# MicronetToNMEA.net
KiCad netlist of a schematic drawn in EasyEDA Pro
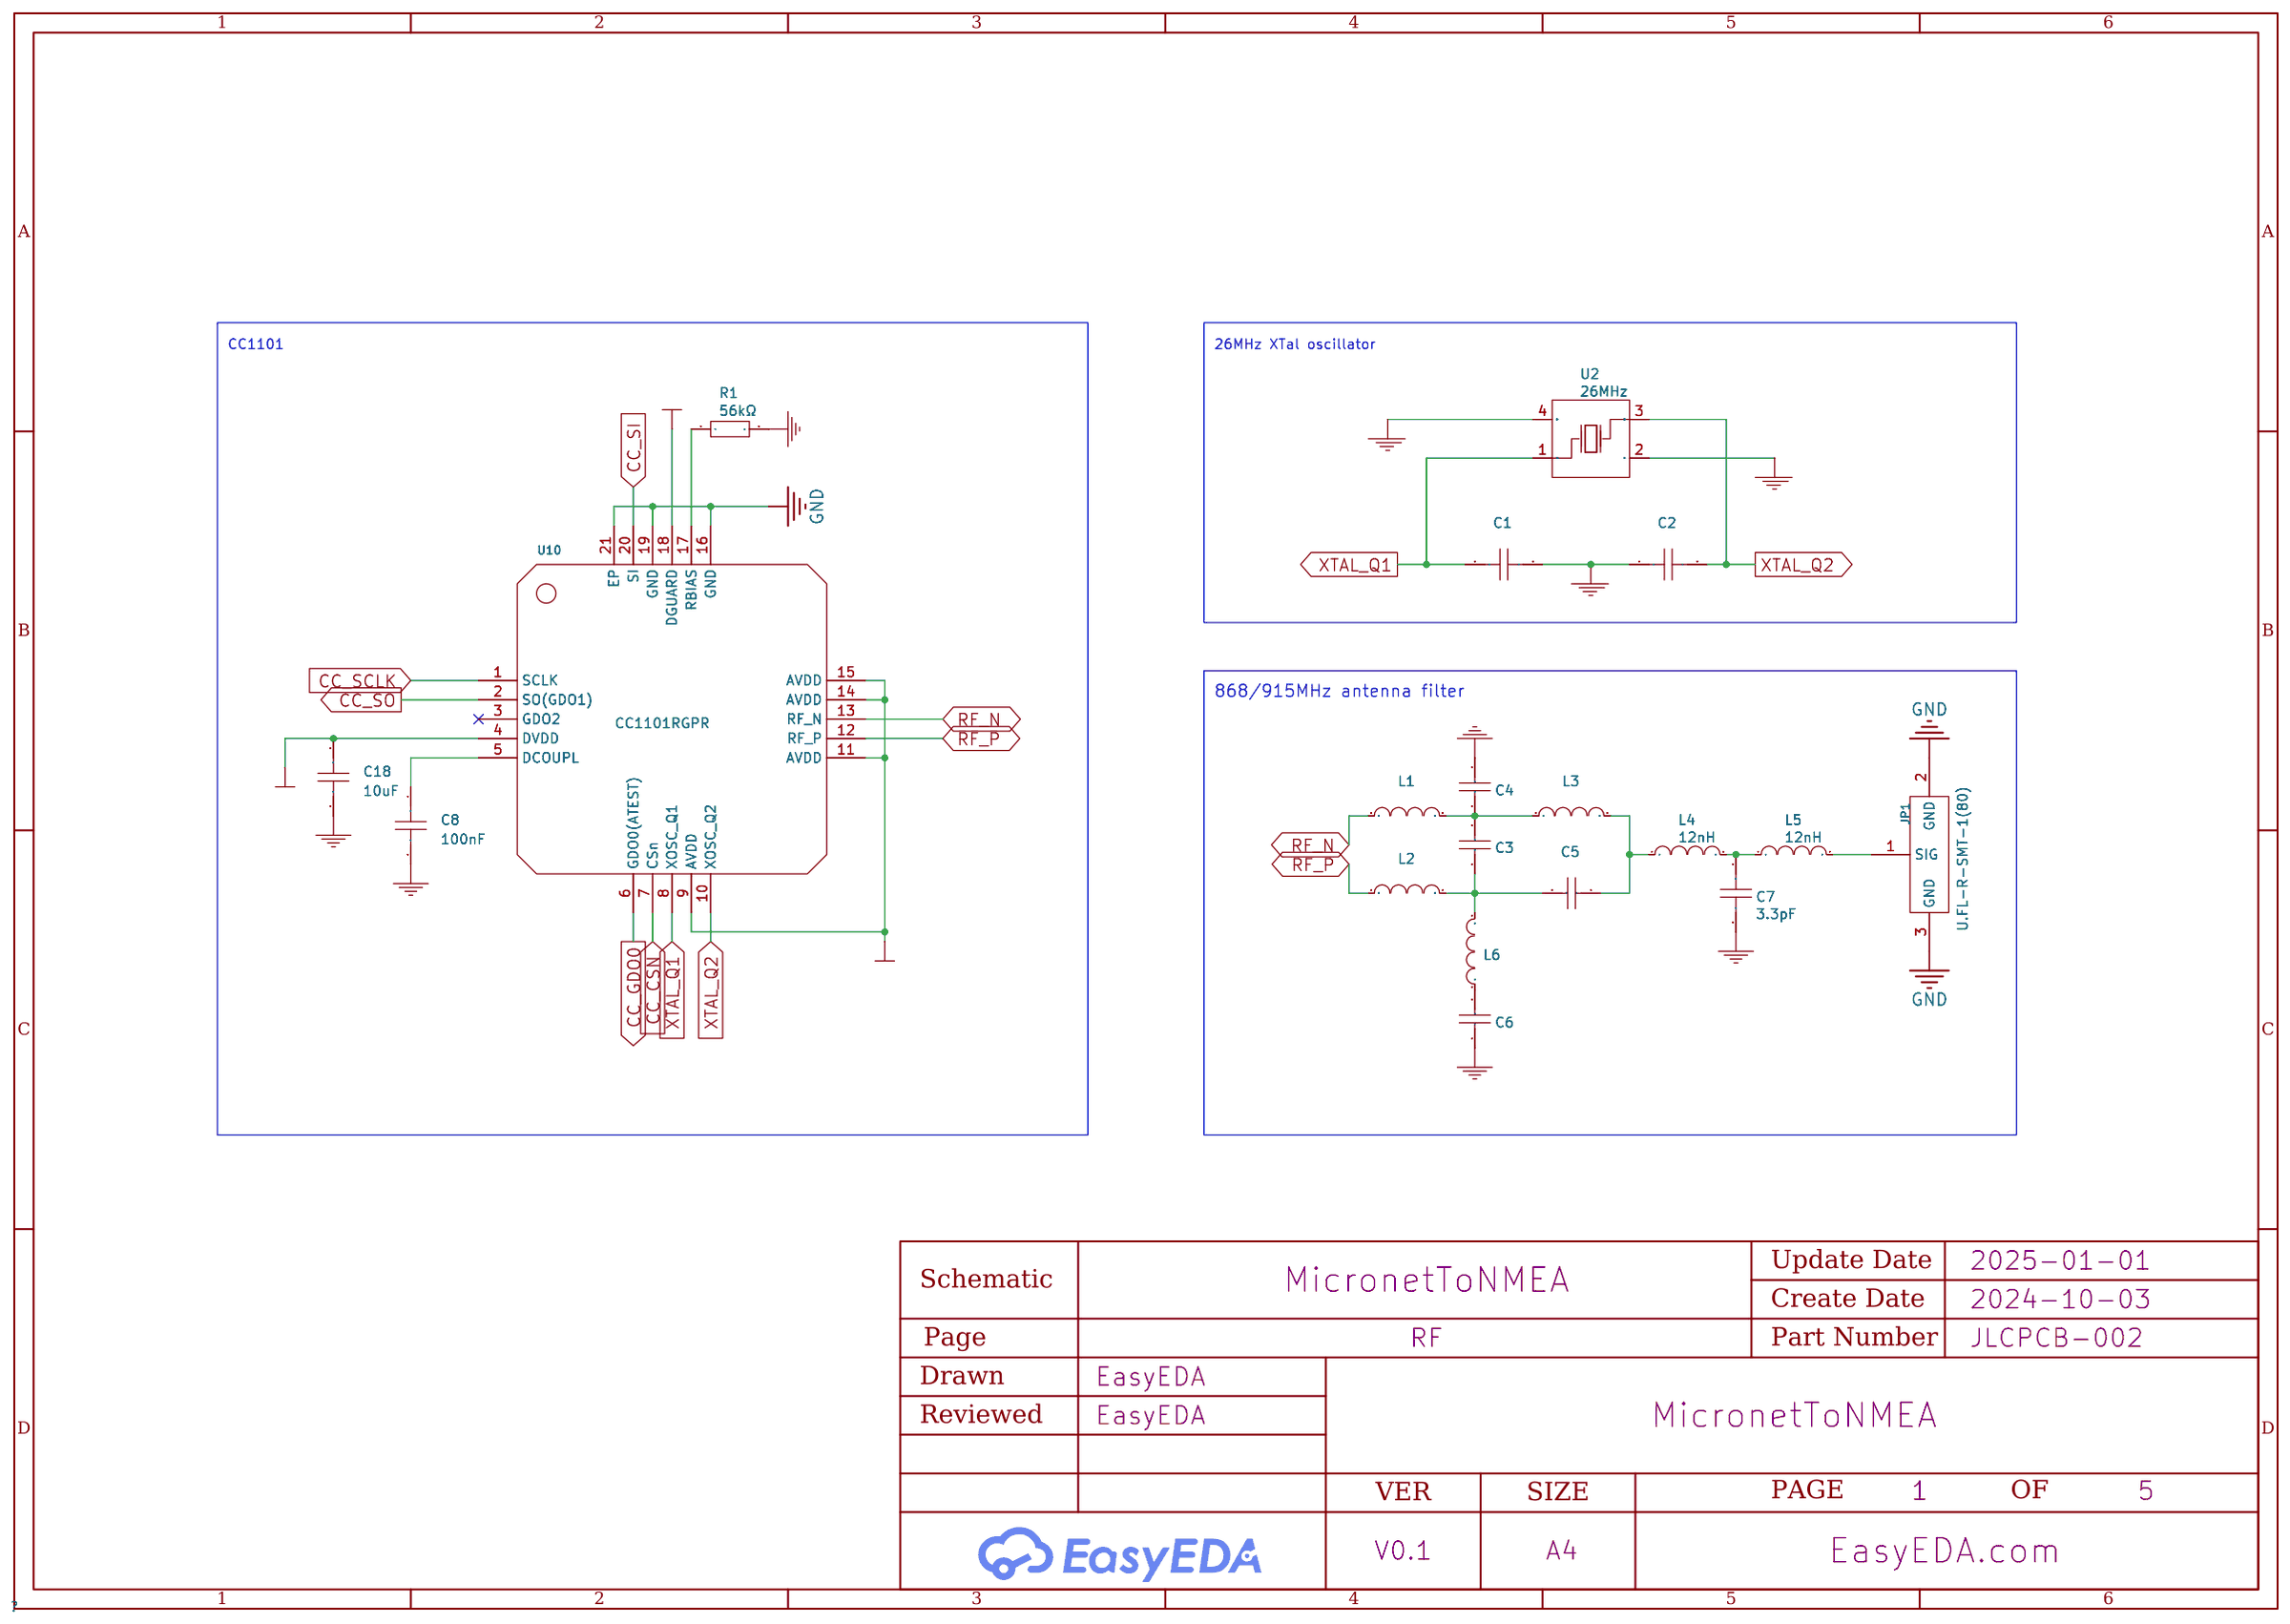
[diagram p0: RF]
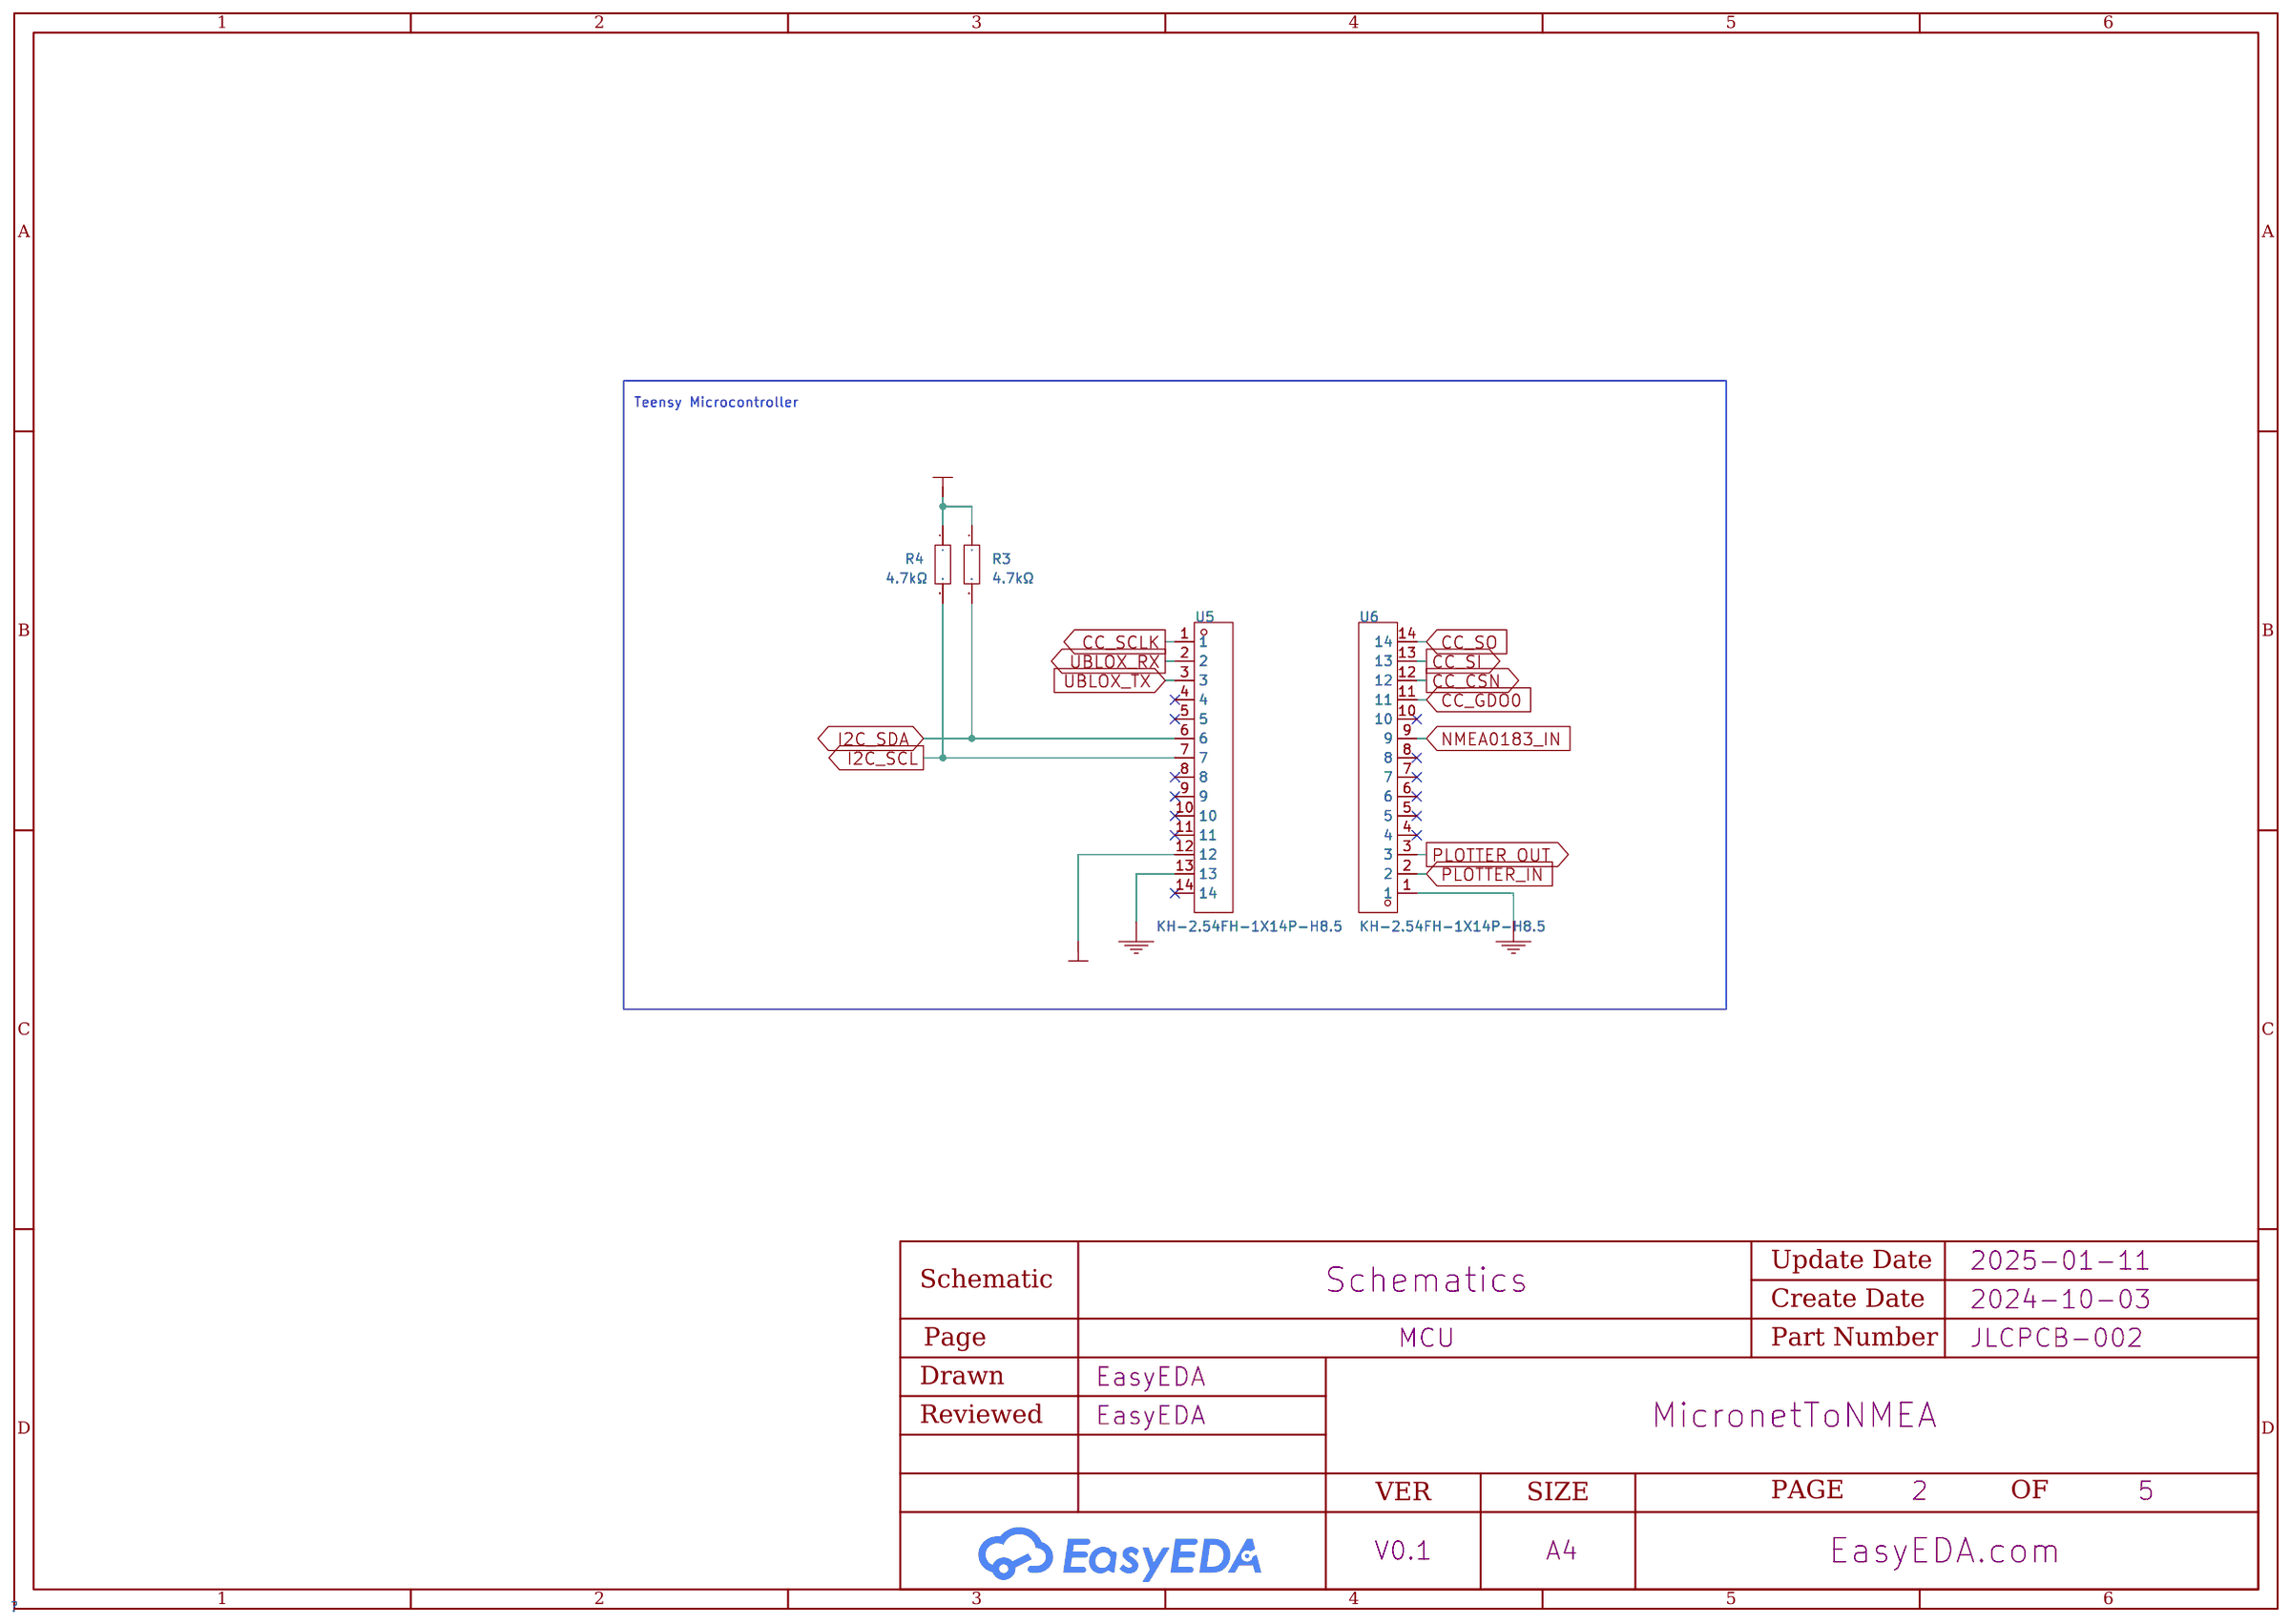
[diagram p1: MCU]
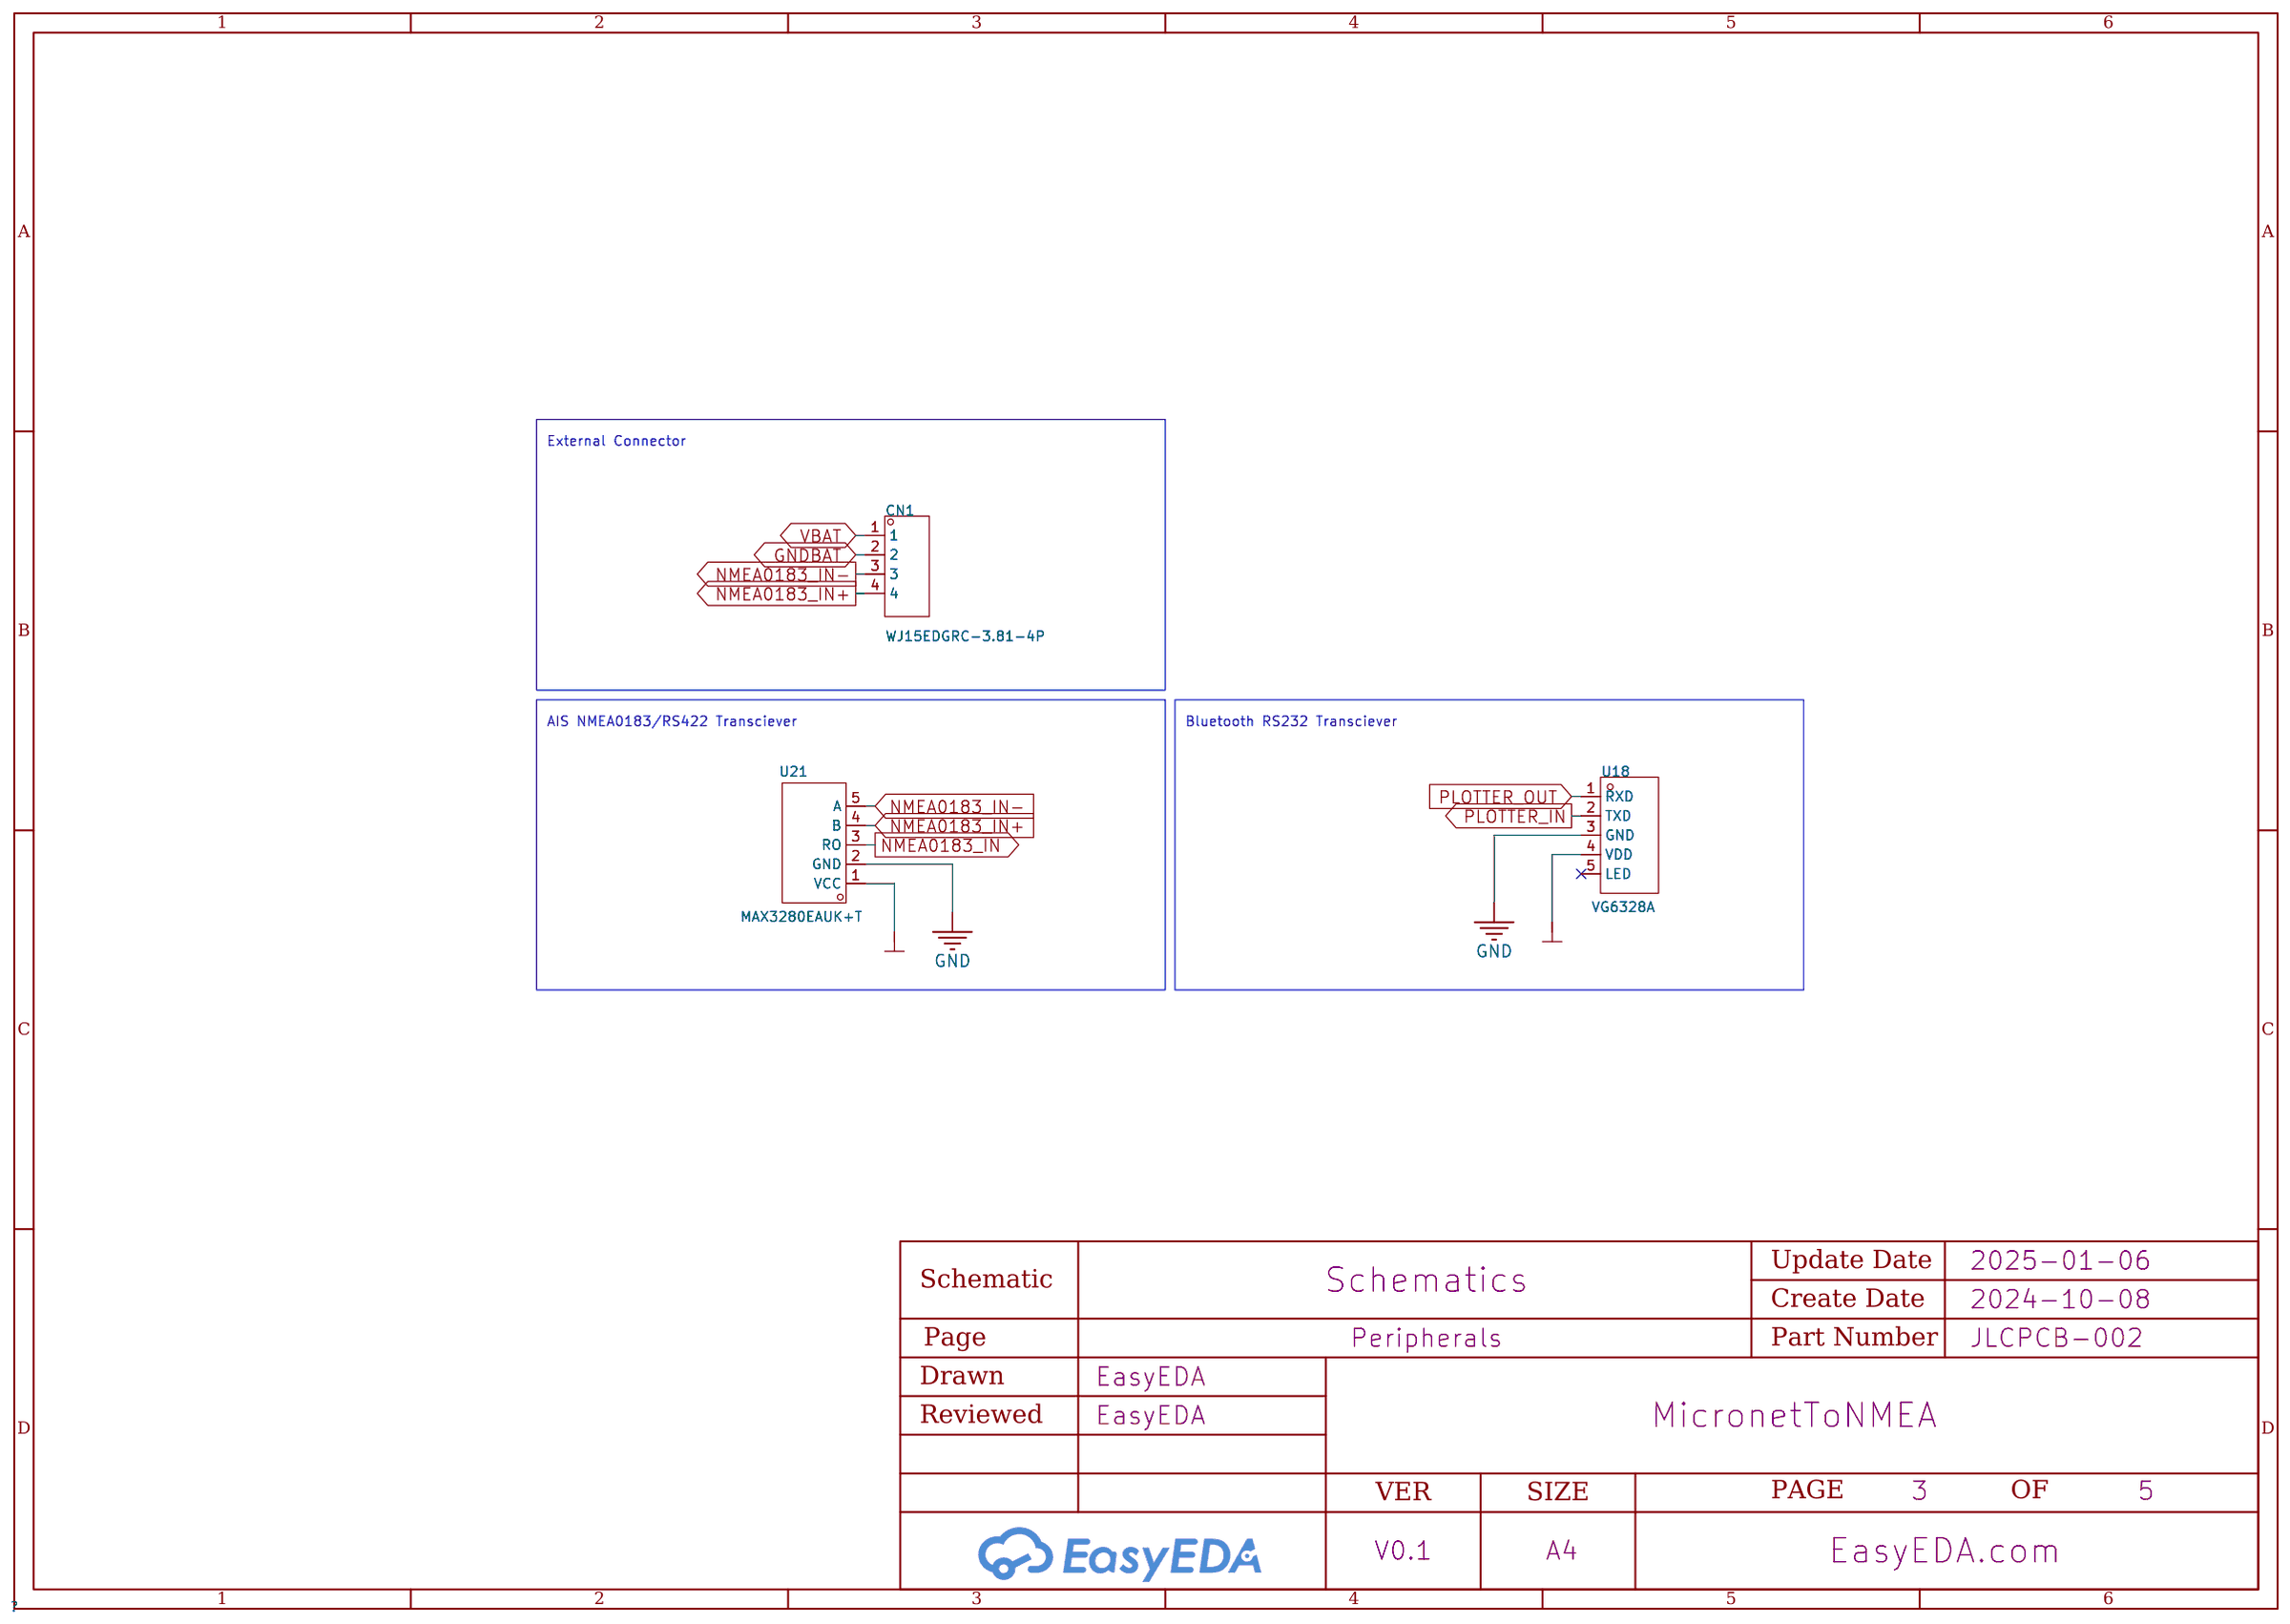
[diagram p2: Peripherals]
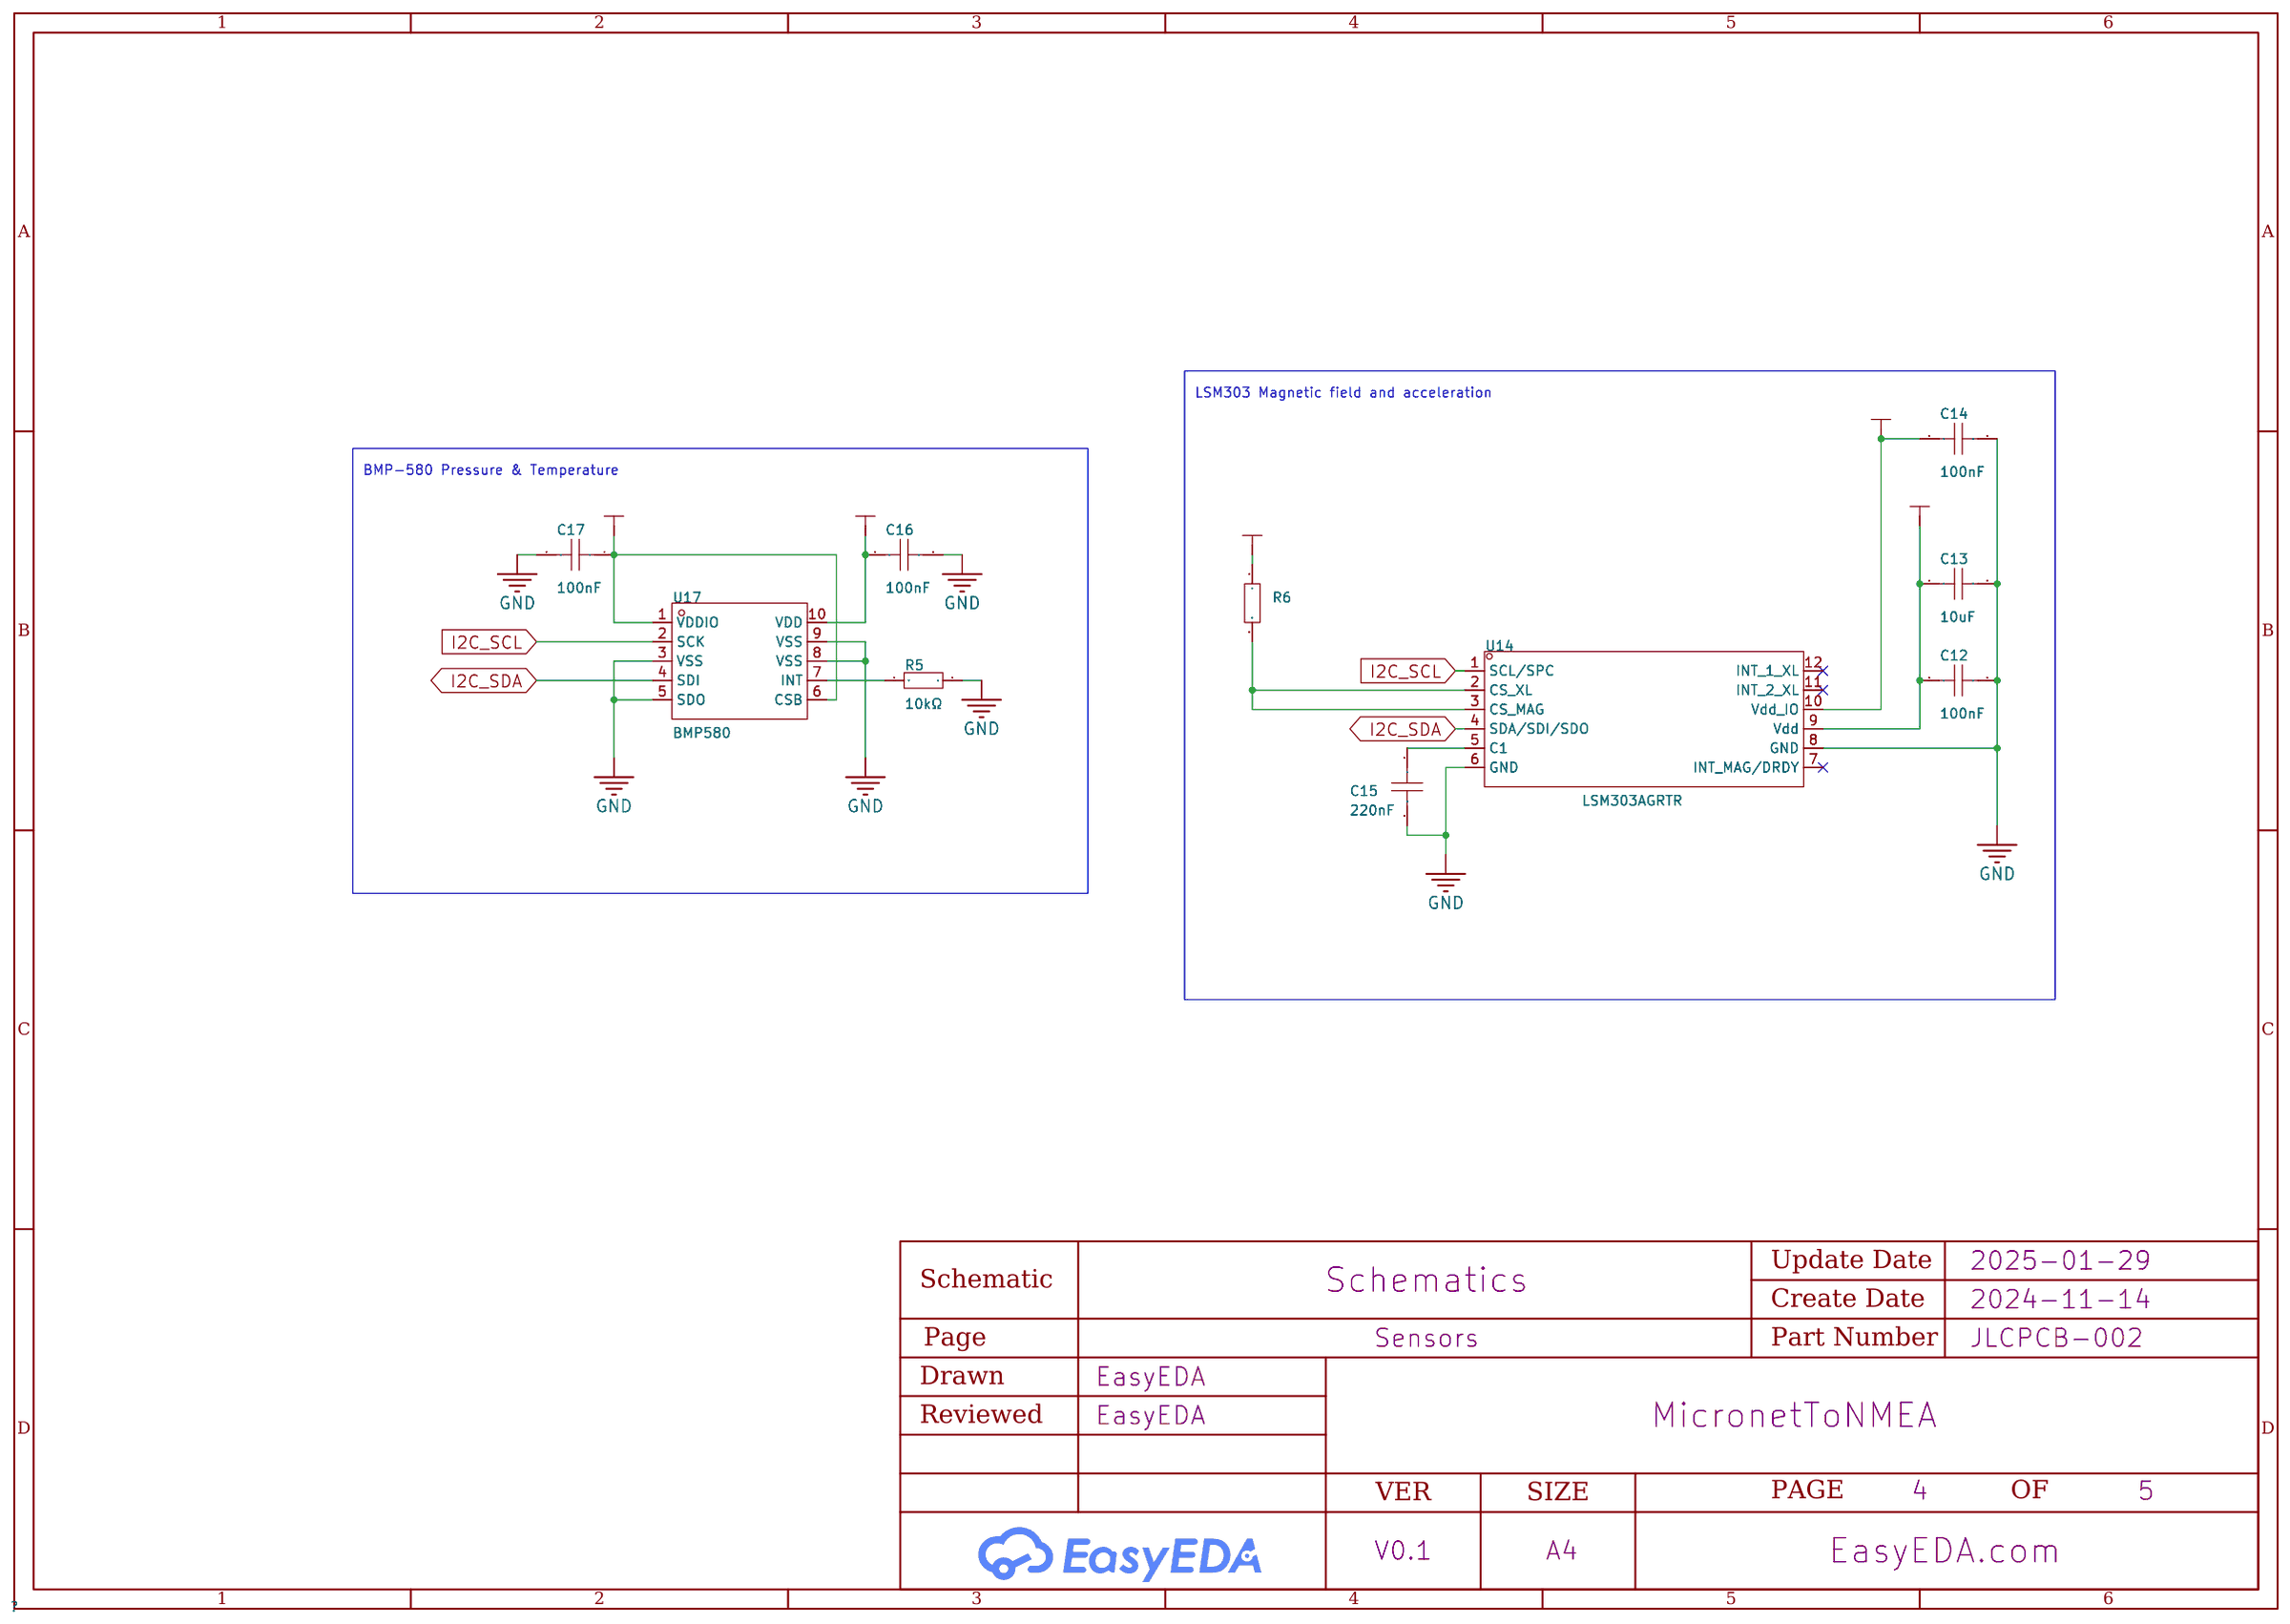
[diagram p3: Sensors]
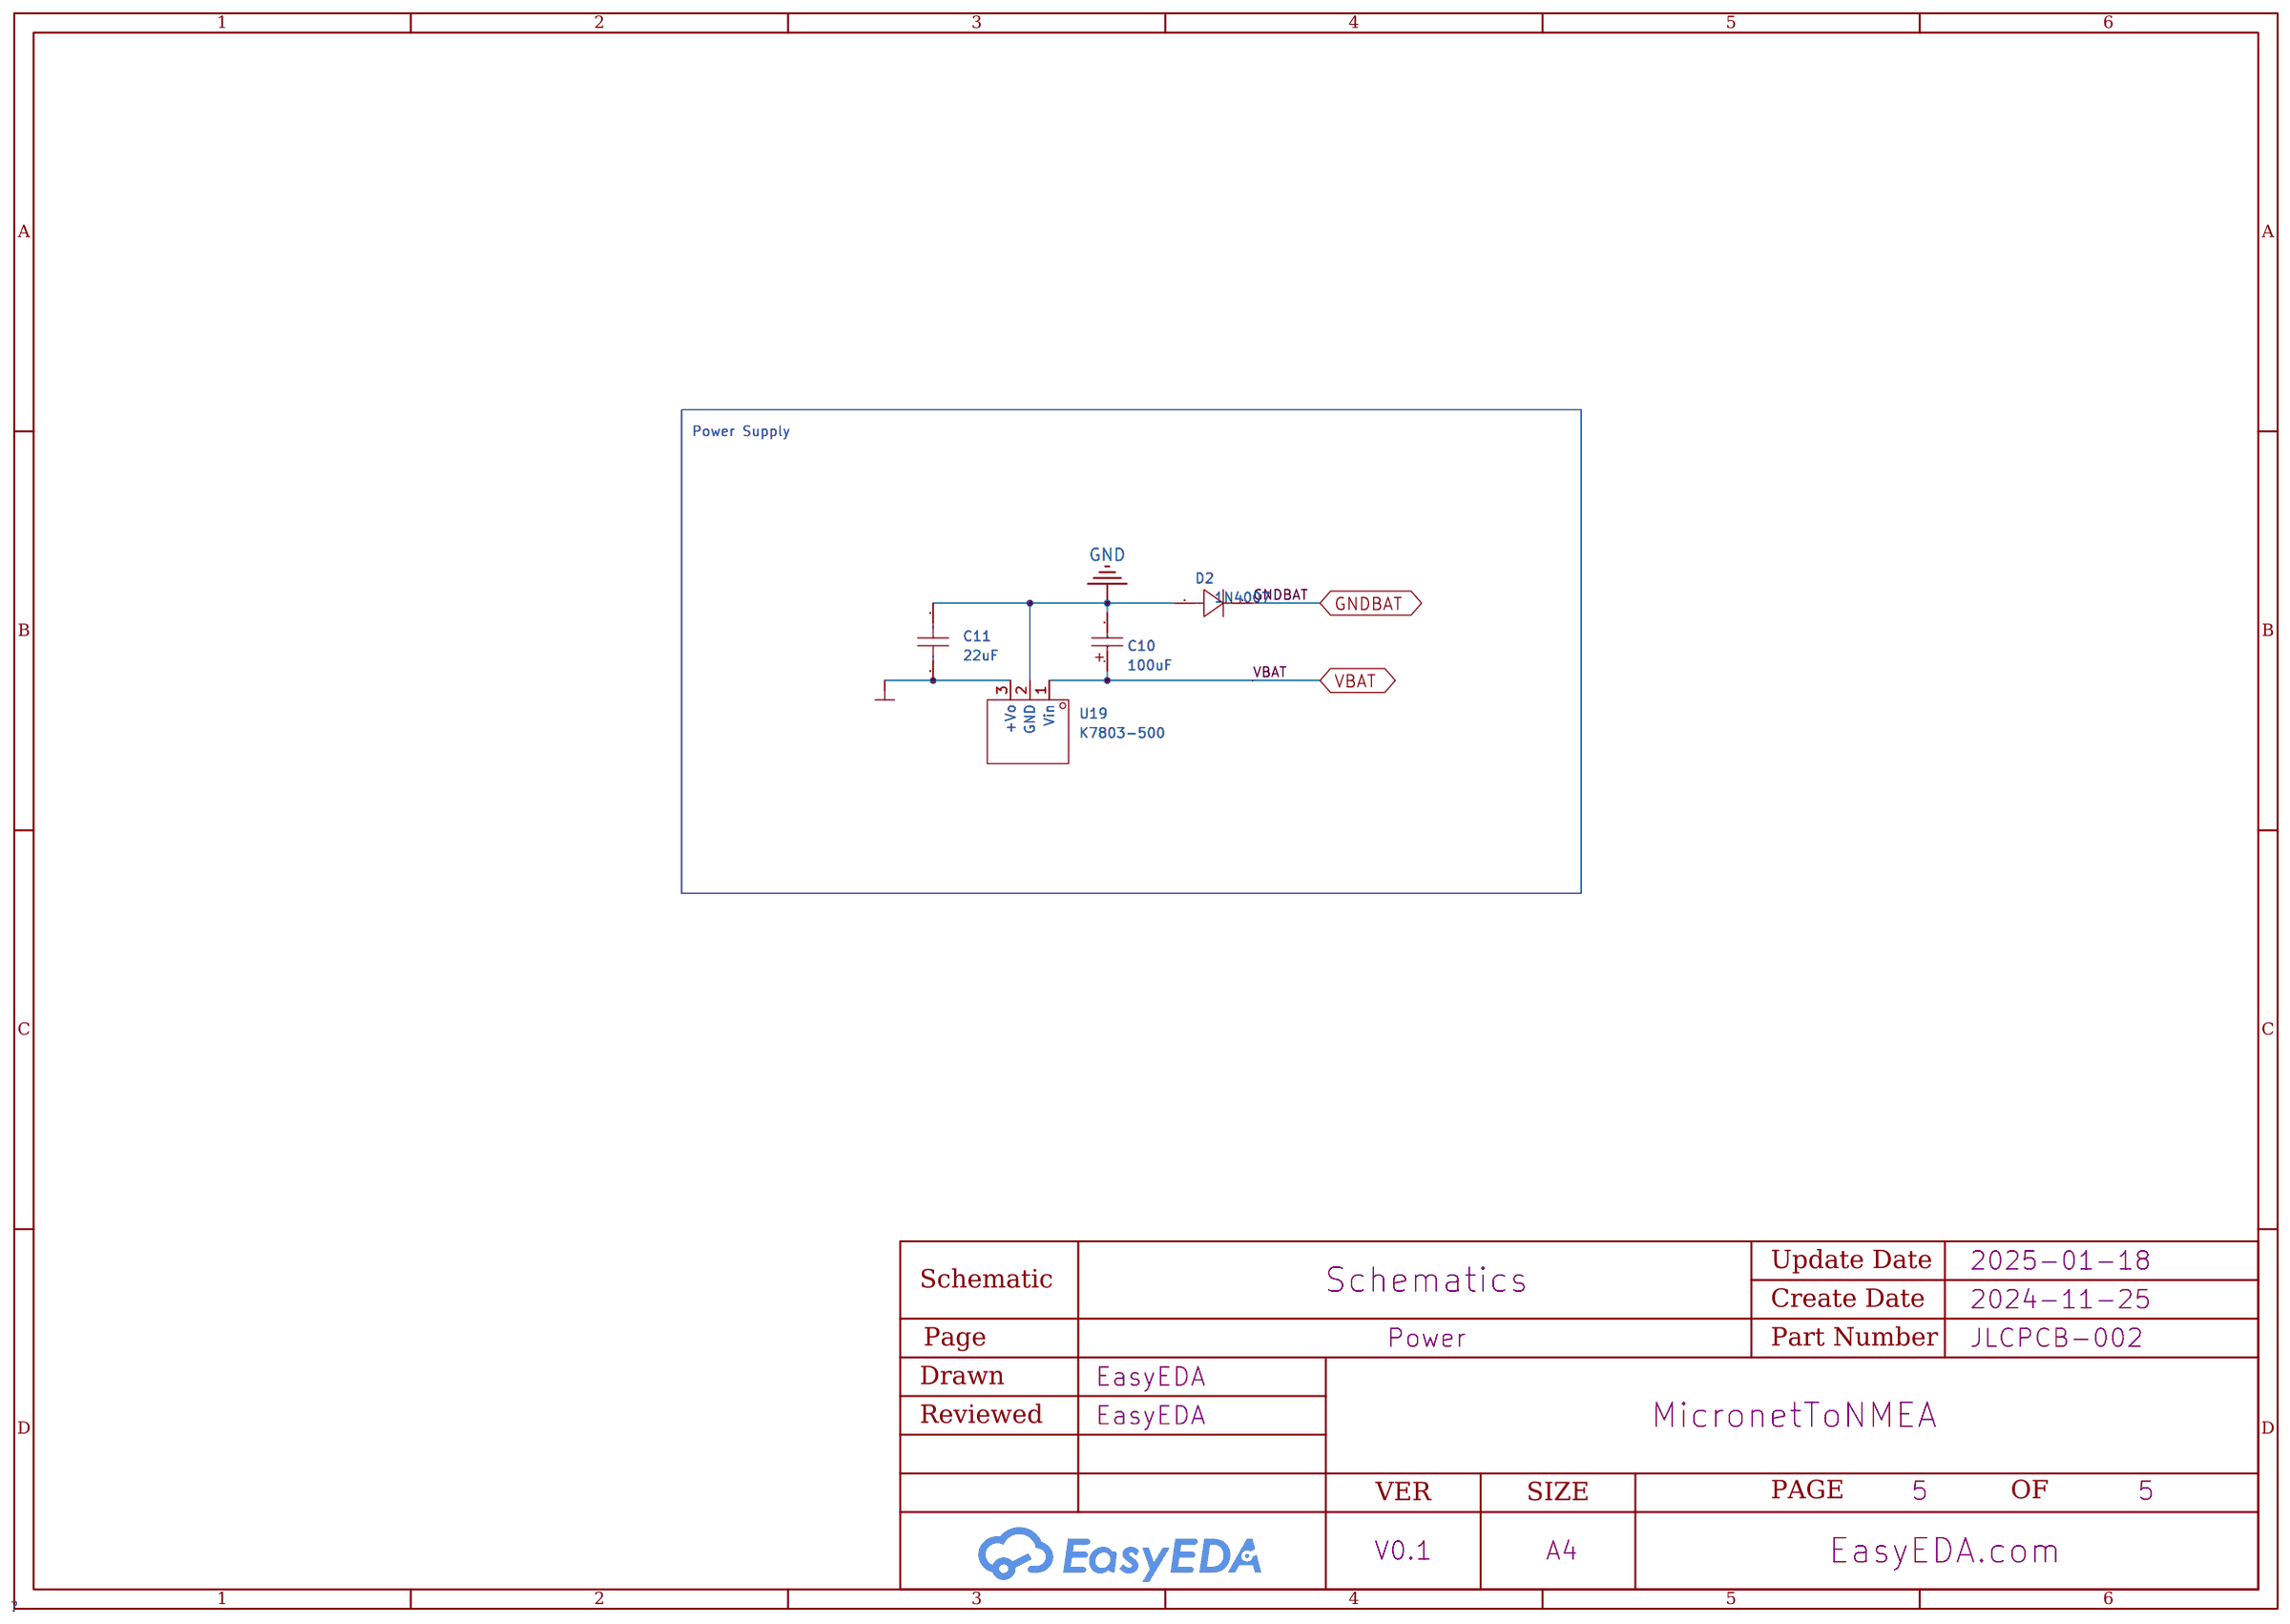
[diagram p4: Power]

(export (version "E")
  (design (tool "Eeschema 10.0.6"))
  (components
    (comp (ref "C1")
      (value "27pF")
      (footprint "easyedapro:C0402")
      (fields
        (field (name "Manufacturer Part") "GJM1555C1H270FB01D")
        (field (name "Manufacturer") "muRata(村田)")
      )
      (libsource (lib "easyedapro") (part "GJM1555C1H270FB01D"))
    )
    (comp (ref "C2")
      (value "27pF")
      (footprint "easyedapro:C0402")
      (fields
        (field (name "Manufacturer Part") "GJM1555C1H270FB01D")
        (field (name "Manufacturer") "muRata(村田)")
      )
      (libsource (lib "easyedapro") (part "GJM1555C1H270FB01D"))
    )
    (comp (ref "C3")
      (value "1pF")
      (footprint "easyedapro:C0402")
      (fields
        (field (name "Manufacturer Part") "GRM1555C1H1R0CA01D")
        (field (name "Manufacturer") "muRata(村田)")
      )
      (libsource (lib "easyedapro") (part "GRM1555C1H1R0CA01D"))
    )
    (comp (ref "C4")
      (value "1.5pF")
      (footprint "easyedapro:C0402")
      (fields
        (field (name "Manufacturer Part") "GRM1555C1H1R5BA01D")
        (field (name "Manufacturer") "muRata(村田)")
      )
      (libsource (lib "easyedapro") (part "GRM1555C1H1R5BA01D"))
    )
    (comp (ref "C5")
      (value "1.5pF")
      (footprint "easyedapro:C0402")
      (fields
        (field (name "Manufacturer Part") "GRM1555C1H1R5BA01D")
        (field (name "Manufacturer") "muRata(村田)")
      )
      (libsource (lib "easyedapro") (part "GRM1555C1H1R5BA01D"))
    )
    (comp (ref "C6")
      (value "100pF")
      (footprint "easyedapro:C0402")
      (fields
        (field (name "Manufacturer Part") "GRM1555C1H101JA01D")
        (field (name "Manufacturer") "muRata(村田)")
      )
      (libsource (lib "easyedapro") (part "GRM1555C1H101JA01D"))
    )
    (comp (ref "C7")
      (value "3.3pF")
      (fields (field (name "Manufacturer") "muRata(村田)"))
      (libsource (lib "easyedapro") (part "3.3pF"))
    )
    (comp (ref "C8")
      (value "100nF")
      (footprint "easyedapro:C0402")
      (fields
        (field (name "Manufacturer Part") "GRM155R62A104KE14D")
        (field (name "Manufacturer") "muRata(村田)")
      )
      (libsource (lib "easyedapro") (part "GRM155R62A104KE14D"))
    )
    (comp (ref "C18")
      (value "10uF")
      (footprint "easyedapro:C0402")
      (fields
        (field (name "Manufacturer Part") "GRM155R61A106ME44D")
        (field (name "Manufacturer") "muRata(村田)")
      )
      (libsource (lib "easyedapro") (part "CAP"))
    )
    (comp (ref "JP1")
      (value "U.FL-R-SMT-1(80)")
      (footprint "easyedapro:RF-SMD_FRF05002-JSS103M")
      (fields (field (name "Manufacturer") "HRS(广濑)"))
      (libsource (lib "easyedapro") (part "U.FL-R-SMT-1(80)"))
    )
    (comp (ref "L1")
      (value "12nH")
      (footprint "easyedapro:L0402")
      (fields (field (name "Manufacturer Part") "LQW15AN12NJ00D") (field (name "Manufacturer") "muRata(村田)"))
      (libsource (lib "easyedapro") (part "LQW15AN12NJ00D"))
    )
    (comp (ref "L2")
      (value "12nH")
      (footprint "easyedapro:L0402")
      (fields (field (name "Manufacturer Part") "LQW15AN12NJ00D") (field (name "Manufacturer") "muRata(村田)"))
      (libsource (lib "easyedapro") (part "LQW15AN12NJ00D"))
    )
    (comp (ref "L3")
      (value "18nH")
      (footprint "easyedapro:IND-SMD_L1.0-W0.5-2")
      (fields (field (name "Manufacturer Part") "LQW15AN18NG00D") (field (name "Manufacturer") "muRata(村田)"))
      (libsource (lib "easyedapro") (part "LQW15AN18NG00D"))
    )
    (comp (ref "L4")
      (value "12nH")
      (footprint "easyedapro:L0402")
      (fields (field (name "Manufacturer Part") "LQW15AN12NG00D") (field (name "Manufacturer") "muRata(村田)"))
      (libsource (lib "easyedapro") (part "LQW15AN12NG00D"))
    )
    (comp (ref "L5")
      (value "12nH")
      (footprint "easyedapro:L0402")
      (fields (field (name "Manufacturer Part") "LQW15AN12NG00D") (field (name "Manufacturer") "muRata(村田)"))
      (libsource (lib "easyedapro") (part "LQW15AN12NG00D"))
    )
    (comp (ref "L6")
      (value "18nH")
      (footprint "easyedapro:IND-SMD_L1.0-W0.5-2")
      (fields (field (name "Manufacturer Part") "LQW15AN18NG00D") (field (name "Manufacturer") "muRata(村田)"))
      (libsource (lib "easyedapro") (part "LQW15AN18NG00D"))
    )
    (comp (ref "R1")
      (value "56kΩ")
      (footprint "easyedapro:R0402")
      (fields (field (name "Manufacturer Part") "RK73H1ETTP5602F") (field (name "Manufacturer") "KOA"))
      (libsource (lib "easyedapro") (part "RK73H1ETTP5602F"))
    )
    (comp (ref "U2")
      (value "26MHz")
      (fields (field (name "Manufacturer Part") "NX3225GA-26MHZ-TI") (field (name "Manufacturer") "NDK"))
      (libsource (lib "easyedapro") (part "26MHz"))
    )
    (comp (ref "U10")
      (value "CC1101RGPR")
      (footprint "easyedapro:QFN-20_L4.0-W4.0-P0.5-TL-EP")
      (fields (field (name "Manufacturer") "TI(德州仪器)"))
      (libsource (lib "easyedapro") (part "CC1101RGPR"))
    )
    (comp (ref "R3")
      (value "4.7kΩ")
      (footprint "easyedapro:R0402")
      (fields
        (field (name "Manufacturer Part") "0402WGF4701TCE")
        (field (name "Manufacturer") "UNI-ROYAL(厚声)")
      )
      (libsource (lib "easyedapro") (part "Res"))
    )
    (comp (ref "R4")
      (value "4.7kΩ")
      (footprint "easyedapro:R0402")
      (fields
        (field (name "Manufacturer Part") "0402WGF4701TCE")
        (field (name "Manufacturer") "UNI-ROYAL(厚声)")
      )
      (libsource (lib "easyedapro") (part "Res"))
    )
    (comp (ref "U5")
      (value "KH-2.54FH-1X14P-H8.5")
      (footprint "easyedapro:HDR-TH_14P-P2.54-V-F")
      (fields (field (name "Manufacturer") "kinghelm(金航标)"))
      (libsource (lib "easyedapro") (part "BX-PM2.54-1-14PY"))
    )
    (comp (ref "U6")
      (value "KH-2.54FH-1X14P-H8.5")
      (footprint "easyedapro:HDR-TH_14P-P2.54-V-F")
      (fields (field (name "Manufacturer") "kinghelm(金航标)"))
      (libsource (lib "easyedapro") (part "BX-PM2.54-1-14PY"))
    )
    (comp (ref "CN1")
      (value "WJ15EDGRC-3.81-4P")
      (footprint "easyedapro:CONN-TH_WJ15EDGRC-3.81-4P")
      (fields (field (name "Manufacturer") "KANGNEX(康奈克斯电气)"))
      (libsource (lib "easyedapro") (part "WJ15EDGRC-3.81-4P"))
    )
    (comp (ref "U18")
      (value "VG6328A")
      (footprint "easyedapro:COMM-SMD_VG6328A")
      (fields (field (name "Manufacturer") "Vollgo(沃进)"))
      (libsource (lib "easyedapro") (part "VG6328A"))
    )
    (comp (ref "U21")
      (value "MAX3280EAUK+T")
      (footprint "easyedapro:SOT-23-5_L3.0-W1.7-P0.95-LS2.8-BL")
      (fields (field (name "Manufacturer") "ADI(亚德诺)/MAXIM(美信)"))
      (libsource (lib "easyedapro") (part "MAX3280EAUK+T"))
    )
    (comp (ref "C12")
      (value "100nF")
      (footprint "easyedapro:C0402")
      (fields
        (field (name "Manufacturer Part") "CL05B104KO5NNNC")
        (field (name "Manufacturer") "SAMSUNG(三星)")
      )
      (libsource (lib "easyedapro") (part "CAP"))
    )
    (comp (ref "C13")
      (value "10uF")
      (footprint "easyedapro:C0402")
      (fields
        (field (name "Manufacturer Part") "GRM155R60J106ME44D")
        (field (name "Manufacturer") "muRata(村田)")
      )
      (libsource (lib "easyedapro") (part "CAP"))
    )
    (comp (ref "C14")
      (value "100nF")
      (footprint "easyedapro:C0402")
      (fields
        (field (name "Manufacturer Part") "CL05B104KO5NNNC")
        (field (name "Manufacturer") "SAMSUNG(三星)")
      )
      (libsource (lib "easyedapro") (part "CAP"))
    )
    (comp (ref "C15")
      (value "220nF")
      (footprint "easyedapro:C0402")
      (fields
        (field (name "Manufacturer Part") "CL05B224KO5NNNC")
        (field (name "Manufacturer") "SAMSUNG(三星)")
      )
      (libsource (lib "easyedapro") (part "CAP"))
    )
    (comp (ref "C16")
      (value "100nF")
      (footprint "easyedapro:C0402")
      (fields
        (field (name "Manufacturer Part") "GRM155R62A104KE14D")
        (field (name "Manufacturer") "SAMSUNG(三星)")
      )
      (libsource (lib "easyedapro") (part "GRM155R62A104KE14D"))
    )
    (comp (ref "C17")
      (value "100nF")
      (footprint "easyedapro:C0402")
      (fields
        (field (name "Manufacturer Part") "GRM155R62A104KE14D")
        (field (name "Manufacturer") "SAMSUNG(三星)")
      )
      (libsource (lib "easyedapro") (part "GRM155R62A104KE14D"))
    )
    (comp (ref "R5")
      (value "10kΩ")
      (footprint "easyedapro:R0402")
      (fields
        (field (name "Manufacturer Part") "0402WGJ0103TCE")
        (field (name "Manufacturer") "UNI-ROYAL(厚声)")
      )
      (libsource (lib "easyedapro") (part "Res"))
    )
    (comp (ref "R6")
      (value "10kΩ")
      (footprint "easyedapro:R0402")
      (fields (field (name "Manufacturer") "UNI-ROYAL(厚声)"))
      (libsource (lib "easyedapro") (part "Res"))
    )
    (comp (ref "U14")
      (value "LSM303AGRTR")
      (footprint "easyedapro:LGA-12_L2.0-W2.0-P0.50-BL")
      (description "Sensor Type:加速度传感器 Operating Temperature:-40°C~+85°C Operating Temperature:-40°C~+85°C")
      (fields (field (name "Manufacturer") "ST(意法半导体)"))
      (libsource (lib "easyedapro") (part "LSM303AGRTR"))
    )
    (comp (ref "U17")
      (value "BMP580")
      (footprint "easyedapro:LGA-10_L2.0-W2.0-P0.50-TL_BMP580")
      (fields (field (name "Manufacturer") "Bosch(博世)"))
      (libsource (lib "easyedapro") (part "BMP580"))
    )
    (comp (ref "C10")
      (value "100uF")
      (footprint "easyedapro:CAP-SMD_BD3.0-L3.3-W3.3-RD")
      (fields (field (name "Manufacturer Part") "EEEFK1H101P") (field (name "Manufacturer") "PANASONIC(松下)"))
      (libsource (lib "easyedapro") (part "C_Ele_SMD"))
    )
    (comp (ref "C11")
      (value "22uF")
      (footprint "easyedapro:C0402")
      (fields
        (field (name "Manufacturer Part") "CL10A226MO7JZNC")
        (field (name "Manufacturer") "SAMSUNG(三星)")
      )
      (libsource (lib "easyedapro") (part "CAP"))
    )
    (comp (ref "D2")
      (value "1N4007")
      (footprint "easyedapro:DO-41_BD2.4-L4.7-P8.70-D0.9-RD")
      (fields (field (name "Manufacturer") "TWGMC(台湾迪嘉)"))
      (libsource (lib "easyedapro") (part "D_1N4007"))
    )
    (comp (ref "U19")
      (value "K7803-500")
      (footprint "easyedapro:PWRM-TH_K78XX-500R3")
      (fields (field (name "Manufacturer") "DEXU(德旭电子)"))
      (libsource (lib "easyedapro") (part "K7803-500R3_C909766"))
    )
  )
  (nets
    (net (code "1") (name "+3.3V") (class "Default")
      (node (ref "C11") (pin "2") (pinfunction "2_2") (pintype "input"))
      (node (ref "C12") (pin "1") (pinfunction "1_1") (pintype "input"))
      (node (ref "C13") (pin "1") (pinfunction "1_1") (pintype "input"))
      (node (ref "C14") (pin "2") (pinfunction "2_2") (pintype "input"))
      (node (ref "C16") (pin "1") (pinfunction "1_1") (pintype "input"))
      (node (ref "C17") (pin "1") (pinfunction "1_1") (pintype "input"))
      (node (ref "C18") (pin "2") (pinfunction "2_2") (pintype "input"))
      (node (ref "R3") (pin "1") (pinfunction "1_1") (pintype "input"))
      (node (ref "R4") (pin "1") (pinfunction "1_1") (pintype "input"))
      (node (ref "R6") (pin "1") (pinfunction "1_1") (pintype "input"))
      (node (ref "U10") (pin "11") (pinfunction "AVDD_11") (pintype "input"))
      (node (ref "U10") (pin "14") (pinfunction "AVDD_14") (pintype "input"))
      (node (ref "U10") (pin "15") (pinfunction "AVDD_15") (pintype "input"))
      (node (ref "U10") (pin "18") (pinfunction "DGUARD_18") (pintype "input"))
      (node (ref "U10") (pin "4") (pinfunction "DVDD_4") (pintype "input"))
      (node (ref "U10") (pin "9") (pinfunction "AVDD_9") (pintype "input"))
      (node (ref "U14") (pin "10") (pinfunction "Vdd_IO_10") (pintype "unspecified"))
      (node (ref "U14") (pin "9") (pinfunction "Vdd_9") (pintype "unspecified"))
      (node (ref "U17") (pin "1") (pinfunction "VDDIO_1") (pintype "unspecified"))
      (node (ref "U17") (pin "10") (pinfunction "VDD_10") (pintype "unspecified"))
      (node (ref "U17") (pin "6") (pinfunction "CSB_6") (pintype "unspecified"))
      (node (ref "U18") (pin "4") (pinfunction "VDD_4") (pintype "unspecified"))
      (node (ref "U19") (pin "3") (pinfunction "+Vo_3") (pintype "unspecified"))
      (node (ref "U21") (pin "1") (pinfunction "VCC_1") (pintype "unspecified"))
      (node (ref "U5") (pin "12") (pinfunction "12_12") (pintype "unspecified"))
    )
    (net (code "2") (name "CC_CSN") (class "Default")
      (node (ref "U10") (pin "7") (pinfunction "CSn_7") (pintype "input"))
      (node (ref "U6") (pin "12") (pinfunction "12_12") (pintype "unspecified"))
    )
    (net (code "3") (name "CC_GDO0") (class "Default")
      (node (ref "U10") (pin "6") (pinfunction "GDO0(ATEST)_6") (pintype "input"))
      (node (ref "U6") (pin "11") (pinfunction "11_11") (pintype "unspecified"))
    )
    (net (code "4") (name "CC_SCLK") (class "Default")
      (node (ref "U10") (pin "1") (pinfunction "SCLK_1") (pintype "input"))
      (node (ref "U5") (pin "1") (pinfunction "1_1") (pintype "unspecified"))
    )
    (net (code "5") (name "CC_SI") (class "Default")
      (node (ref "U10") (pin "20") (pinfunction "SI_20") (pintype "input"))
      (node (ref "U6") (pin "13") (pinfunction "13_13") (pintype "unspecified"))
    )
    (net (code "6") (name "CC_SO") (class "Default")
      (node (ref "U10") (pin "2") (pinfunction "SO(GDO1)_2") (pintype "input"))
      (node (ref "U6") (pin "14") (pinfunction "14_14") (pintype "unspecified"))
    )
    (net (code "7") (name "GND") (class "Default")
      (node (ref "C1") (pin "2") (pinfunction "2_2") (pintype "input"))
      (node (ref "C10") (pin "2") (pinfunction "2_2") (pintype "input"))
      (node (ref "C11") (pin "1") (pinfunction "1_1") (pintype "input"))
      (node (ref "C12") (pin "2") (pinfunction "2_2") (pintype "input"))
      (node (ref "C13") (pin "2") (pinfunction "2_2") (pintype "input"))
      (node (ref "C14") (pin "1") (pinfunction "1_1") (pintype "input"))
      (node (ref "C15") (pin "2") (pinfunction "2_2") (pintype "input"))
      (node (ref "C16") (pin "2") (pinfunction "2_2") (pintype "input"))
      (node (ref "C17") (pin "2") (pinfunction "2_2") (pintype "input"))
      (node (ref "C18") (pin "1") (pinfunction "1_1") (pintype "input"))
      (node (ref "C2") (pin "1") (pinfunction "1_1") (pintype "input"))
      (node (ref "C4") (pin "2") (pinfunction "2_2") (pintype "input"))
      (node (ref "C6") (pin "2") (pinfunction "2_2") (pintype "input"))
      (node (ref "C7") (pin "2") (pinfunction "2_2") (pintype "unspecified"))
      (node (ref "C8") (pin "2") (pinfunction "2_2") (pintype "input"))
      (node (ref "D2") (pin "2") (pinfunction "A_2") (pintype "input"))
      (node (ref "JP1") (pin "2") (pinfunction "GND_2") (pintype "input"))
      (node (ref "JP1") (pin "3") (pinfunction "GND_3") (pintype "input"))
      (node (ref "R1") (pin "2") (pinfunction "2_2") (pintype "input"))
      (node (ref "R5") (pin "1") (pinfunction "1_1") (pintype "input"))
      (node (ref "U10") (pin "16") (pinfunction "GND_16") (pintype "input"))
      (node (ref "U10") (pin "19") (pinfunction "GND_19") (pintype "input"))
      (node (ref "U10") (pin "21") (pinfunction "EP_21") (pintype "input"))
      (node (ref "U14") (pin "6") (pinfunction "GND_6") (pintype "unspecified"))
      (node (ref "U14") (pin "8") (pinfunction "GND_8") (pintype "unspecified"))
      (node (ref "U17") (pin "3") (pinfunction "VSS_3") (pintype "unspecified"))
      (node (ref "U17") (pin "5") (pinfunction "SDO_5") (pintype "unspecified"))
      (node (ref "U17") (pin "8") (pinfunction "VSS_8") (pintype "unspecified"))
      (node (ref "U17") (pin "9") (pinfunction "VSS_9") (pintype "unspecified"))
      (node (ref "U18") (pin "3") (pinfunction "GND_3") (pintype "unspecified"))
      (node (ref "U19") (pin "2") (pinfunction "GND_2") (pintype "unspecified"))
      (node (ref "U2") (pin "2") (pinfunction "GND_2") (pintype "unspecified"))
      (node (ref "U2") (pin "4") (pinfunction "GND_4") (pintype "unspecified"))
      (node (ref "U21") (pin "2") (pinfunction "GND_2") (pintype "unspecified"))
      (node (ref "U5") (pin "13") (pinfunction "13_13") (pintype "unspecified"))
      (node (ref "U6") (pin "1") (pinfunction "1_1") (pintype "unspecified"))
    )
    (net (code "8") (name "GNDBAT") (class "Default")
      (node (ref "CN1") (pin "2") (pinfunction "2_2") (pintype "unspecified"))
      (node (ref "D2") (pin "1") (pinfunction "K_1") (pintype "input"))
    )
    (net (code "9") (name "I2C_SCL") (class "Default")
      (node (ref "R4") (pin "2") (pinfunction "2_2") (pintype "input"))
      (node (ref "U14") (pin "1") (pinfunction "SCL/SPC_1") (pintype "unspecified"))
      (node (ref "U17") (pin "2") (pinfunction "SCK_2") (pintype "unspecified"))
      (node (ref "U5") (pin "7") (pinfunction "7_7") (pintype "unspecified"))
    )
    (net (code "10") (name "I2C_SDA") (class "Default")
      (node (ref "R3") (pin "2") (pinfunction "2_2") (pintype "input"))
      (node (ref "U14") (pin "4") (pinfunction "SDA/SDI/SDO_4") (pintype "unspecified"))
      (node (ref "U17") (pin "4") (pinfunction "SDI_4") (pintype "unspecified"))
      (node (ref "U5") (pin "6") (pinfunction "6_6") (pintype "unspecified"))
    )
    (net (code "11") (name "NMEA0183_IN") (class "Default")
      (node (ref "U21") (pin "3") (pinfunction "RO_3") (pintype "unspecified"))
      (node (ref "U6") (pin "9") (pinfunction "9_9") (pintype "unspecified"))
    )
    (net (code "12") (name "NMEA0183_IN+") (class "Default")
      (node (ref "CN1") (pin "4") (pinfunction "4_4") (pintype "unspecified"))
      (node (ref "U21") (pin "4") (pinfunction "B_4") (pintype "unspecified"))
    )
    (net (code "13") (name "NMEA0183_IN-") (class "Default")
      (node (ref "CN1") (pin "3") (pinfunction "3_3") (pintype "unspecified"))
      (node (ref "U21") (pin "5") (pinfunction "A_5") (pintype "unspecified"))
    )
    (net (code "14") (name "Net-(C3-Pad1)") (class "Default")
      (node (ref "C3") (pin "1") (pinfunction "1_1") (pintype "input"))
      (node (ref "C5") (pin "2") (pinfunction "2_2") (pintype "input"))
      (node (ref "L2") (pin "2") (pinfunction "2_2") (pintype "input"))
      (node (ref "L6") (pin "2") (pinfunction "2_2") (pintype "input"))
    )
    (net (code "15") (name "Net-(C3-Pad2)") (class "Default")
      (node (ref "C3") (pin "2") (pinfunction "2_2") (pintype "input"))
      (node (ref "C4") (pin "1") (pinfunction "1_1") (pintype "input"))
      (node (ref "L1") (pin "2") (pinfunction "2_2") (pintype "input"))
      (node (ref "L3") (pin "1") (pinfunction "1_1") (pintype "input"))
    )
    (net (code "16") (name "Net-(C5-Pad1)") (class "Default")
      (node (ref "C5") (pin "1") (pinfunction "1_1") (pintype "input"))
      (node (ref "L3") (pin "2") (pinfunction "2_2") (pintype "input"))
      (node (ref "L4") (pin "1") (pinfunction "1_1") (pintype "unspecified"))
    )
    (net (code "17") (name "Net-(C6-Pad1)") (class "Default")
      (node (ref "C6") (pin "1") (pinfunction "1_1") (pintype "input"))
      (node (ref "L6") (pin "1") (pinfunction "1_1") (pintype "input"))
    )
    (net (code "18") (name "Net-(C7-Pad1)") (class "Default")
      (node (ref "C7") (pin "1") (pinfunction "1_1") (pintype "unspecified"))
      (node (ref "L4") (pin "2") (pinfunction "2_2") (pintype "unspecified"))
      (node (ref "L5") (pin "1") (pinfunction "1_1") (pintype "unspecified"))
    )
    (net (code "19") (name "Net-(JP1-SIG)") (class "Default")
      (node (ref "JP1") (pin "1") (pinfunction "SIG_1") (pintype "input"))
      (node (ref "L5") (pin "2") (pinfunction "2_2") (pintype "unspecified"))
    )
    (net (code "20") (name "Net-(U10-DCOUPL)") (class "Default")
      (node (ref "C8") (pin "1") (pinfunction "1_1") (pintype "input"))
      (node (ref "U10") (pin "5") (pinfunction "DCOUPL_5") (pintype "input"))
    )
    (net (code "21") (name "Net-(U10-RBIAS)") (class "Default")
      (node (ref "R1") (pin "1") (pinfunction "1_1") (pintype "input"))
      (node (ref "U10") (pin "17") (pinfunction "RBIAS_17") (pintype "input"))
    )
    (net (code "22") (name "Net-(U14-C1)") (class "Default")
      (node (ref "C15") (pin "1") (pinfunction "1_1") (pintype "input"))
      (node (ref "U14") (pin "5") (pinfunction "C1_5") (pintype "unspecified"))
    )
    (net (code "23") (name "Net-(U14-CS_MAG)") (class "Default")
      (node (ref "R6") (pin "2") (pinfunction "2_2") (pintype "input"))
      (node (ref "U14") (pin "2") (pinfunction "CS_XL_2") (pintype "unspecified"))
      (node (ref "U14") (pin "3") (pinfunction "CS_MAG_3") (pintype "unspecified"))
    )
    (net (code "24") (name "Net-(U17-INT)") (class "Default")
      (node (ref "R5") (pin "2") (pinfunction "2_2") (pintype "input"))
      (node (ref "U17") (pin "7") (pinfunction "INT_7") (pintype "unspecified"))
    )
    (net (code "25") (name "PLOTTER_IN") (class "Default")
      (node (ref "U18") (pin "2") (pinfunction "TXD_2") (pintype "unspecified"))
      (node (ref "U6") (pin "2") (pinfunction "2_2") (pintype "unspecified"))
    )
    (net (code "26") (name "PLOTTER_OUT") (class "Default")
      (node (ref "U18") (pin "1") (pinfunction "RXD_1") (pintype "unspecified"))
      (node (ref "U6") (pin "3") (pinfunction "3_3") (pintype "unspecified"))
    )
    (net (code "27") (name "RF_N") (class "Default")
      (node (ref "L1") (pin "1") (pinfunction "1_1") (pintype "input"))
      (node (ref "U10") (pin "13") (pinfunction "RF_N_13") (pintype "input"))
    )
    (net (code "28") (name "RF_P") (class "Default")
      (node (ref "L2") (pin "1") (pinfunction "1_1") (pintype "input"))
      (node (ref "U10") (pin "12") (pinfunction "RF_P_12") (pintype "input"))
    )
    (net (code "29") (name "UBLOX_RX") (class "Default")
      (node (ref "U5") (pin "2") (pinfunction "2_2") (pintype "unspecified"))
    )
    (net (code "30") (name "UBLOX_TX") (class "Default")
      (node (ref "U5") (pin "3") (pinfunction "3_3") (pintype "unspecified"))
    )
    (net (code "31") (name "VBAT") (class "Default")
      (node (ref "C10") (pin "1") (pinfunction "1_1") (pintype "input"))
      (node (ref "CN1") (pin "1") (pinfunction "1_1") (pintype "unspecified"))
      (node (ref "U19") (pin "1") (pinfunction "Vin_1") (pintype "unspecified"))
    )
    (net (code "32") (name "XTAL_Q1") (class "Default")
      (node (ref "C1") (pin "1") (pinfunction "1_1") (pintype "input"))
      (node (ref "U10") (pin "8") (pinfunction "XOSC_Q1_8") (pintype "input"))
      (node (ref "U2") (pin "1") (pinfunction "OSC1_1") (pintype "unspecified"))
    )
    (net (code "33") (name "XTAL_Q2") (class "Default")
      (node (ref "C2") (pin "2") (pinfunction "2_2") (pintype "input"))
      (node (ref "U10") (pin "10") (pinfunction "XOSC_Q2_10") (pintype "input"))
      (node (ref "U2") (pin "3") (pinfunction "OSC2_3") (pintype "unspecified"))
    )
    (net (code "34") (name "unconnected-(U5-Pad4)") (class "Default")
      (node (ref "U5") (pin "4") (pinfunction "4_4") (pintype "unspecified+no_connect"))
    )
    (net (code "35") (name "unconnected-(U5-Pad5)") (class "Default")
      (node (ref "U5") (pin "5") (pinfunction "5_5") (pintype "unspecified+no_connect"))
    )
    (net (code "36") (name "unconnected-(U5-Pad8)") (class "Default")
      (node (ref "U5") (pin "8") (pinfunction "8_8") (pintype "unspecified+no_connect"))
    )
    (net (code "37") (name "unconnected-(U5-Pad9)") (class "Default")
      (node (ref "U5") (pin "9") (pinfunction "9_9") (pintype "unspecified+no_connect"))
    )
    (net (code "38") (name "unconnected-(U5-Pad10)") (class "Default")
      (node (ref "U5") (pin "10") (pinfunction "10_10") (pintype "unspecified+no_connect"))
    )
    (net (code "39") (name "unconnected-(U5-Pad11)") (class "Default")
      (node (ref "U5") (pin "11") (pinfunction "11_11") (pintype "unspecified+no_connect"))
    )
    (net (code "40") (name "unconnected-(U5-Pad14)") (class "Default")
      (node (ref "U5") (pin "14") (pinfunction "14_14") (pintype "unspecified+no_connect"))
    )
    (net (code "41") (name "unconnected-(U6-Pad4)") (class "Default")
      (node (ref "U6") (pin "4") (pinfunction "4_4") (pintype "unspecified+no_connect"))
    )
    (net (code "42") (name "unconnected-(U6-Pad5)") (class "Default")
      (node (ref "U6") (pin "5") (pinfunction "5_5") (pintype "unspecified+no_connect"))
    )
    (net (code "43") (name "unconnected-(U6-Pad6)") (class "Default")
      (node (ref "U6") (pin "6") (pinfunction "6_6") (pintype "unspecified+no_connect"))
    )
    (net (code "44") (name "unconnected-(U6-Pad7)") (class "Default")
      (node (ref "U6") (pin "7") (pinfunction "7_7") (pintype "unspecified+no_connect"))
    )
    (net (code "45") (name "unconnected-(U6-Pad8)") (class "Default")
      (node (ref "U6") (pin "8") (pinfunction "8_8") (pintype "unspecified+no_connect"))
    )
    (net (code "46") (name "unconnected-(U6-Pad10)") (class "Default")
      (node (ref "U6") (pin "10") (pinfunction "10_10") (pintype "unspecified+no_connect"))
    )
    (net (code "47") (name "unconnected-(U10-GDO2-Pad3)") (class "Default")
      (node (ref "U10") (pin "3") (pinfunction "GDO2_3") (pintype "input+no_connect"))
    )
    (net (code "48") (name "unconnected-(U14-INT_1_XL-Pad12)") (class "Default")
      (node (ref "U14") (pin "12") (pinfunction "INT_1_XL_12") (pintype "unspecified+no_connect"))
    )
    (net (code "49") (name "unconnected-(U14-INT_2_XL-Pad11)") (class "Default")
      (node (ref "U14") (pin "11") (pinfunction "INT_2_XL_11") (pintype "unspecified+no_connect"))
    )
    (net (code "50") (name "unconnected-(U14-INT_MAG{slash}DRDY-Pad7)") (class "Default")
      (node (ref "U14") (pin "7") (pinfunction "INT_MAG/DRDY_7") (pintype "unspecified+no_connect"))
    )
    (net (code "51") (name "unconnected-(U18-LED-Pad5)") (class "Default")
      (node (ref "U18") (pin "5") (pinfunction "LED_5") (pintype "unspecified+no_connect"))
    )
  )
)
